# test_esp32.net
KiCad netlist of a schematic drawn in EAGLE
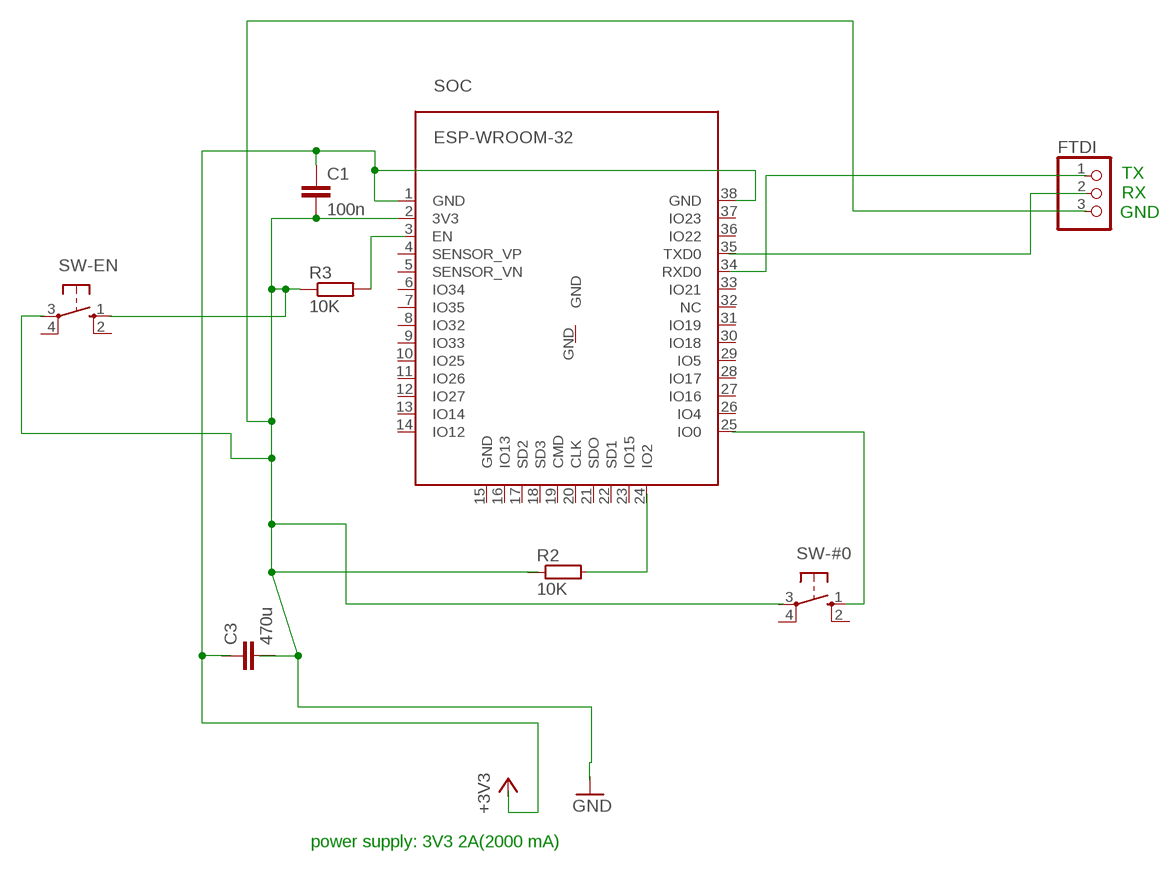
[diagram p0: schematic, sheet 1]

(export (version "E")
  (design (tool "Eeschema 10.0.6"))
  (components
    (comp (ref "C1")
      (value "100n")
      (footprint "eagle-import:C0603")
      (libsource (lib "eagle-import") (part "C-EUC0603"))
    )
    (comp (ref "C3")
      (value "470u")
      (footprint "eagle-import:C1206")
      (libsource (lib "eagle-import") (part "C-EUC1206"))
    )
    (comp (ref "FTDI")
      (value "PINHD-1X3")
      (footprint "eagle-import:1X03")
      (libsource (lib "eagle-import") (part "PINHD-1X3"))
    )
    (comp (ref "R2")
      (value "10K")
      (footprint "eagle-import:R0603")
      (libsource (lib "eagle-import") (part "R-EU_R0603"))
    )
    (comp (ref "R3")
      (value "10K")
      (footprint "eagle-import:R0603")
      (libsource (lib "eagle-import") (part "R-EU_R0603"))
    )
    (comp (ref "SOC")
      (value "ESP-WROOM-32")
      (footprint "eagle-import:ESP-WROOM-32")
      (libsource (lib "eagle-import") (part "ESP-WROOM-32"))
    )
    (comp (ref "SW-#0")
      (value "10-XX")
      (footprint "eagle-import:B3F-10XX")
      (fields (field (name "MPN") "B3F-1000"))
      (libsource (lib "eagle-import") (part "10-XX"))
    )
    (comp (ref "SW-EN")
      (value "10-XX")
      (footprint "eagle-import:B3F-10XX")
      (fields (field (name "MPN") "B3F-1000"))
      (libsource (lib "eagle-import") (part "10-XX"))
    )
  )
  (nets
    (net (code "3") (name "Net-(C1-Pad1)") (class "Default")
      (node (ref "C1") (pin "1") (pinfunction "1_1") (pintype "passive"))
      (node (ref "SOC") (pin "1") (pinfunction "GND_1") (pintype "bidirectional"))
      (node (ref "SOC") (pin "38") (pinfunction "GND_38") (pintype "bidirectional"))
    )
    (net (code "4") (name "Net-(SOC-3V3)") (class "Default")
      (node (ref "C1") (pin "2") (pinfunction "2_2") (pintype "passive"))
      (node (ref "R3") (pin "1") (pinfunction "1_1") (pintype "passive"))
      (node (ref "SOC") (pin "2") (pinfunction "3V3_2") (pintype "bidirectional"))
    )
    (net (code "5") (name "unconnected-(C3-Pad1)") (class "Default")
      (node (ref "C3") (pin "1") (pinfunction "1_1") (pintype "passive"))
    )
    (net (code "6") (name "unconnected-(C3-Pad2)") (class "Default")
      (node (ref "C3") (pin "2") (pinfunction "2_2") (pintype "passive"))
    )
    (net (code "7") (name "unconnected-(FTDI-Pad1)") (class "Default")
      (node (ref "FTDI") (pin "1") (pinfunction "1_1") (pintype "passive"))
    )
    (net (code "8") (name "unconnected-(FTDI-Pad2)") (class "Default")
      (node (ref "FTDI") (pin "2") (pinfunction "2_2") (pintype "passive"))
    )
    (net (code "9") (name "unconnected-(FTDI-Pad3)") (class "Default")
      (node (ref "FTDI") (pin "3") (pinfunction "3_3") (pintype "passive"))
    )
    (net (code "10") (name "unconnected-(R2-Pad1)") (class "Default")
      (node (ref "R2") (pin "1") (pinfunction "1_1") (pintype "passive"))
    )
    (net (code "11") (name "unconnected-(R2-Pad2)") (class "Default")
      (node (ref "R2") (pin "2") (pinfunction "2_2") (pintype "passive"))
    )
    (net (code "12") (name "unconnected-(R3-Pad2)") (class "Default")
      (node (ref "R3") (pin "2") (pinfunction "2_2") (pintype "passive"))
    )
    (net (code "13") (name "unconnected-(SOC-CLK-Pad20)") (class "Default")
      (node (ref "SOC") (pin "20") (pinfunction "CLK_20") (pintype "bidirectional"))
    )
    (net (code "14") (name "unconnected-(SOC-CMD-Pad19)") (class "Default")
      (node (ref "SOC") (pin "19") (pinfunction "CMD_19") (pintype "bidirectional"))
    )
    (net (code "15") (name "unconnected-(SOC-EN-Pad3)") (class "Default")
      (node (ref "SOC") (pin "3") (pinfunction "EN_3") (pintype "bidirectional"))
    )
    (net (code "16") (name "unconnected-(SOC-GND-Pad15)") (class "Default")
      (node (ref "SOC") (pin "15") (pinfunction "GND_15") (pintype "bidirectional"))
    )
    (net (code "17") (name "unconnected-(SOC-IO0-Pad25)") (class "Default")
      (node (ref "SOC") (pin "25") (pinfunction "IO0_25") (pintype "bidirectional"))
    )
    (net (code "18") (name "unconnected-(SOC-IO2-Pad24)") (class "Default")
      (node (ref "SOC") (pin "24") (pinfunction "IO2_24") (pintype "bidirectional"))
    )
    (net (code "19") (name "unconnected-(SOC-IO4-Pad26)") (class "Default")
      (node (ref "SOC") (pin "26") (pinfunction "IO4_26") (pintype "bidirectional"))
    )
    (net (code "20") (name "unconnected-(SOC-IO5-Pad29)") (class "Default")
      (node (ref "SOC") (pin "29") (pinfunction "IO5_29") (pintype "bidirectional"))
    )
    (net (code "21") (name "unconnected-(SOC-IO12-Pad14)") (class "Default")
      (node (ref "SOC") (pin "14") (pinfunction "IO12_14") (pintype "bidirectional"))
    )
    (net (code "22") (name "unconnected-(SOC-IO13-Pad16)") (class "Default")
      (node (ref "SOC") (pin "16") (pinfunction "IO13_16") (pintype "bidirectional"))
    )
    (net (code "23") (name "unconnected-(SOC-IO14-Pad13)") (class "Default")
      (node (ref "SOC") (pin "13") (pinfunction "IO14_13") (pintype "bidirectional"))
    )
    (net (code "24") (name "unconnected-(SOC-IO15-Pad23)") (class "Default")
      (node (ref "SOC") (pin "23") (pinfunction "IO15_23") (pintype "bidirectional"))
    )
    (net (code "25") (name "unconnected-(SOC-IO16-Pad27)") (class "Default")
      (node (ref "SOC") (pin "27") (pinfunction "IO16_27") (pintype "bidirectional"))
    )
    (net (code "26") (name "unconnected-(SOC-IO17-Pad28)") (class "Default")
      (node (ref "SOC") (pin "28") (pinfunction "IO17_28") (pintype "bidirectional"))
    )
    (net (code "27") (name "unconnected-(SOC-IO18-Pad30)") (class "Default")
      (node (ref "SOC") (pin "30") (pinfunction "IO18_30") (pintype "bidirectional"))
    )
    (net (code "28") (name "unconnected-(SOC-IO19-Pad31)") (class "Default")
      (node (ref "SOC") (pin "31") (pinfunction "IO19_31") (pintype "bidirectional"))
    )
    (net (code "29") (name "unconnected-(SOC-IO21-Pad33)") (class "Default")
      (node (ref "SOC") (pin "33") (pinfunction "IO21_33") (pintype "bidirectional"))
    )
    (net (code "30") (name "unconnected-(SOC-IO22-Pad36)") (class "Default")
      (node (ref "SOC") (pin "36") (pinfunction "IO22_36") (pintype "bidirectional"))
    )
    (net (code "31") (name "unconnected-(SOC-IO23-Pad37)") (class "Default")
      (node (ref "SOC") (pin "37") (pinfunction "IO23_37") (pintype "bidirectional"))
    )
    (net (code "32") (name "unconnected-(SOC-IO25-Pad10)") (class "Default")
      (node (ref "SOC") (pin "10") (pinfunction "IO25_10") (pintype "bidirectional"))
    )
    (net (code "33") (name "unconnected-(SOC-IO26-Pad11)") (class "Default")
      (node (ref "SOC") (pin "11") (pinfunction "IO26_11") (pintype "bidirectional"))
    )
    (net (code "34") (name "unconnected-(SOC-IO27-Pad12)") (class "Default")
      (node (ref "SOC") (pin "12") (pinfunction "IO27_12") (pintype "bidirectional"))
    )
    (net (code "35") (name "unconnected-(SOC-IO32-Pad8)") (class "Default")
      (node (ref "SOC") (pin "8") (pinfunction "IO32_8") (pintype "bidirectional"))
    )
    (net (code "36") (name "unconnected-(SOC-IO33-Pad9)") (class "Default")
      (node (ref "SOC") (pin "9") (pinfunction "IO33_9") (pintype "bidirectional"))
    )
    (net (code "37") (name "unconnected-(SOC-IO34-Pad6)") (class "Default")
      (node (ref "SOC") (pin "6") (pinfunction "IO34_6") (pintype "bidirectional"))
    )
    (net (code "38") (name "unconnected-(SOC-IO35-Pad7)") (class "Default")
      (node (ref "SOC") (pin "7") (pinfunction "IO35_7") (pintype "bidirectional"))
    )
    (net (code "39") (name "unconnected-(SOC-NC-Pad32)") (class "Default")
      (node (ref "SOC") (pin "32") (pinfunction "NC_32") (pintype "bidirectional"))
    )
    (net (code "40") (name "unconnected-(SOC-PadGND)") (class "Default")
      (node (ref "SOC") (pin "GND") (pinfunction "GND_GND") (pintype "bidirectional"))
    )
    (net (code "41") (name "unconnected-(SOC-RXD0-Pad34)") (class "Default")
      (node (ref "SOC") (pin "34") (pinfunction "RXD0_34") (pintype "bidirectional"))
    )
    (net (code "42") (name "unconnected-(SOC-SD1-Pad22)") (class "Default")
      (node (ref "SOC") (pin "22") (pinfunction "SD1_22") (pintype "bidirectional"))
    )
    (net (code "43") (name "unconnected-(SOC-SD2-Pad17)") (class "Default")
      (node (ref "SOC") (pin "17") (pinfunction "SD2_17") (pintype "bidirectional"))
    )
    (net (code "44") (name "unconnected-(SOC-SD3-Pad18)") (class "Default")
      (node (ref "SOC") (pin "18") (pinfunction "SD3_18") (pintype "bidirectional"))
    )
    (net (code "45") (name "unconnected-(SOC-SDO-Pad21)") (class "Default")
      (node (ref "SOC") (pin "21") (pinfunction "SDO_21") (pintype "bidirectional"))
    )
    (net (code "46") (name "unconnected-(SOC-SENSOR_VN-Pad5)") (class "Default")
      (node (ref "SOC") (pin "5") (pinfunction "SENSOR_VN_5") (pintype "bidirectional"))
    )
    (net (code "47") (name "unconnected-(SOC-SENSOR_VP-Pad4)") (class "Default")
      (node (ref "SOC") (pin "4") (pinfunction "SENSOR_VP_4") (pintype "bidirectional"))
    )
    (net (code "48") (name "unconnected-(SOC-TXD0-Pad35)") (class "Default")
      (node (ref "SOC") (pin "35") (pinfunction "TXD0_35") (pintype "bidirectional"))
    )
    (net (code "49") (name "unconnected-(SW-#0-P-Pad3)") (class "Default")
      (node (ref "SW-#0") (pin "3") (pinfunction "P_3") (pintype "passive"))
    )
    (net (code "50") (name "unconnected-(SW-#0-P1-Pad4)") (class "Default")
      (node (ref "SW-#0") (pin "4") (pinfunction "P1_4") (pintype "passive"))
    )
    (net (code "51") (name "unconnected-(SW-#0-S-Pad1)") (class "Default")
      (node (ref "SW-#0") (pin "1") (pinfunction "S_1") (pintype "passive"))
    )
    (net (code "52") (name "unconnected-(SW-#0-S1-Pad2)") (class "Default")
      (node (ref "SW-#0") (pin "2") (pinfunction "S1_2") (pintype "passive"))
    )
    (net (code "53") (name "unconnected-(SW-EN-P-Pad3)") (class "Default")
      (node (ref "SW-EN") (pin "3") (pinfunction "P_3") (pintype "passive"))
    )
    (net (code "54") (name "unconnected-(SW-EN-P1-Pad4)") (class "Default")
      (node (ref "SW-EN") (pin "4") (pinfunction "P1_4") (pintype "passive"))
    )
    (net (code "55") (name "unconnected-(SW-EN-S-Pad1)") (class "Default")
      (node (ref "SW-EN") (pin "1") (pinfunction "S_1") (pintype "passive"))
    )
    (net (code "56") (name "unconnected-(SW-EN-S1-Pad2)") (class "Default")
      (node (ref "SW-EN") (pin "2") (pinfunction "S1_2") (pintype "passive"))
    )
  )
)
